# msnanopcb.net
KiCad netlist of a schematic drawn in EAGLE
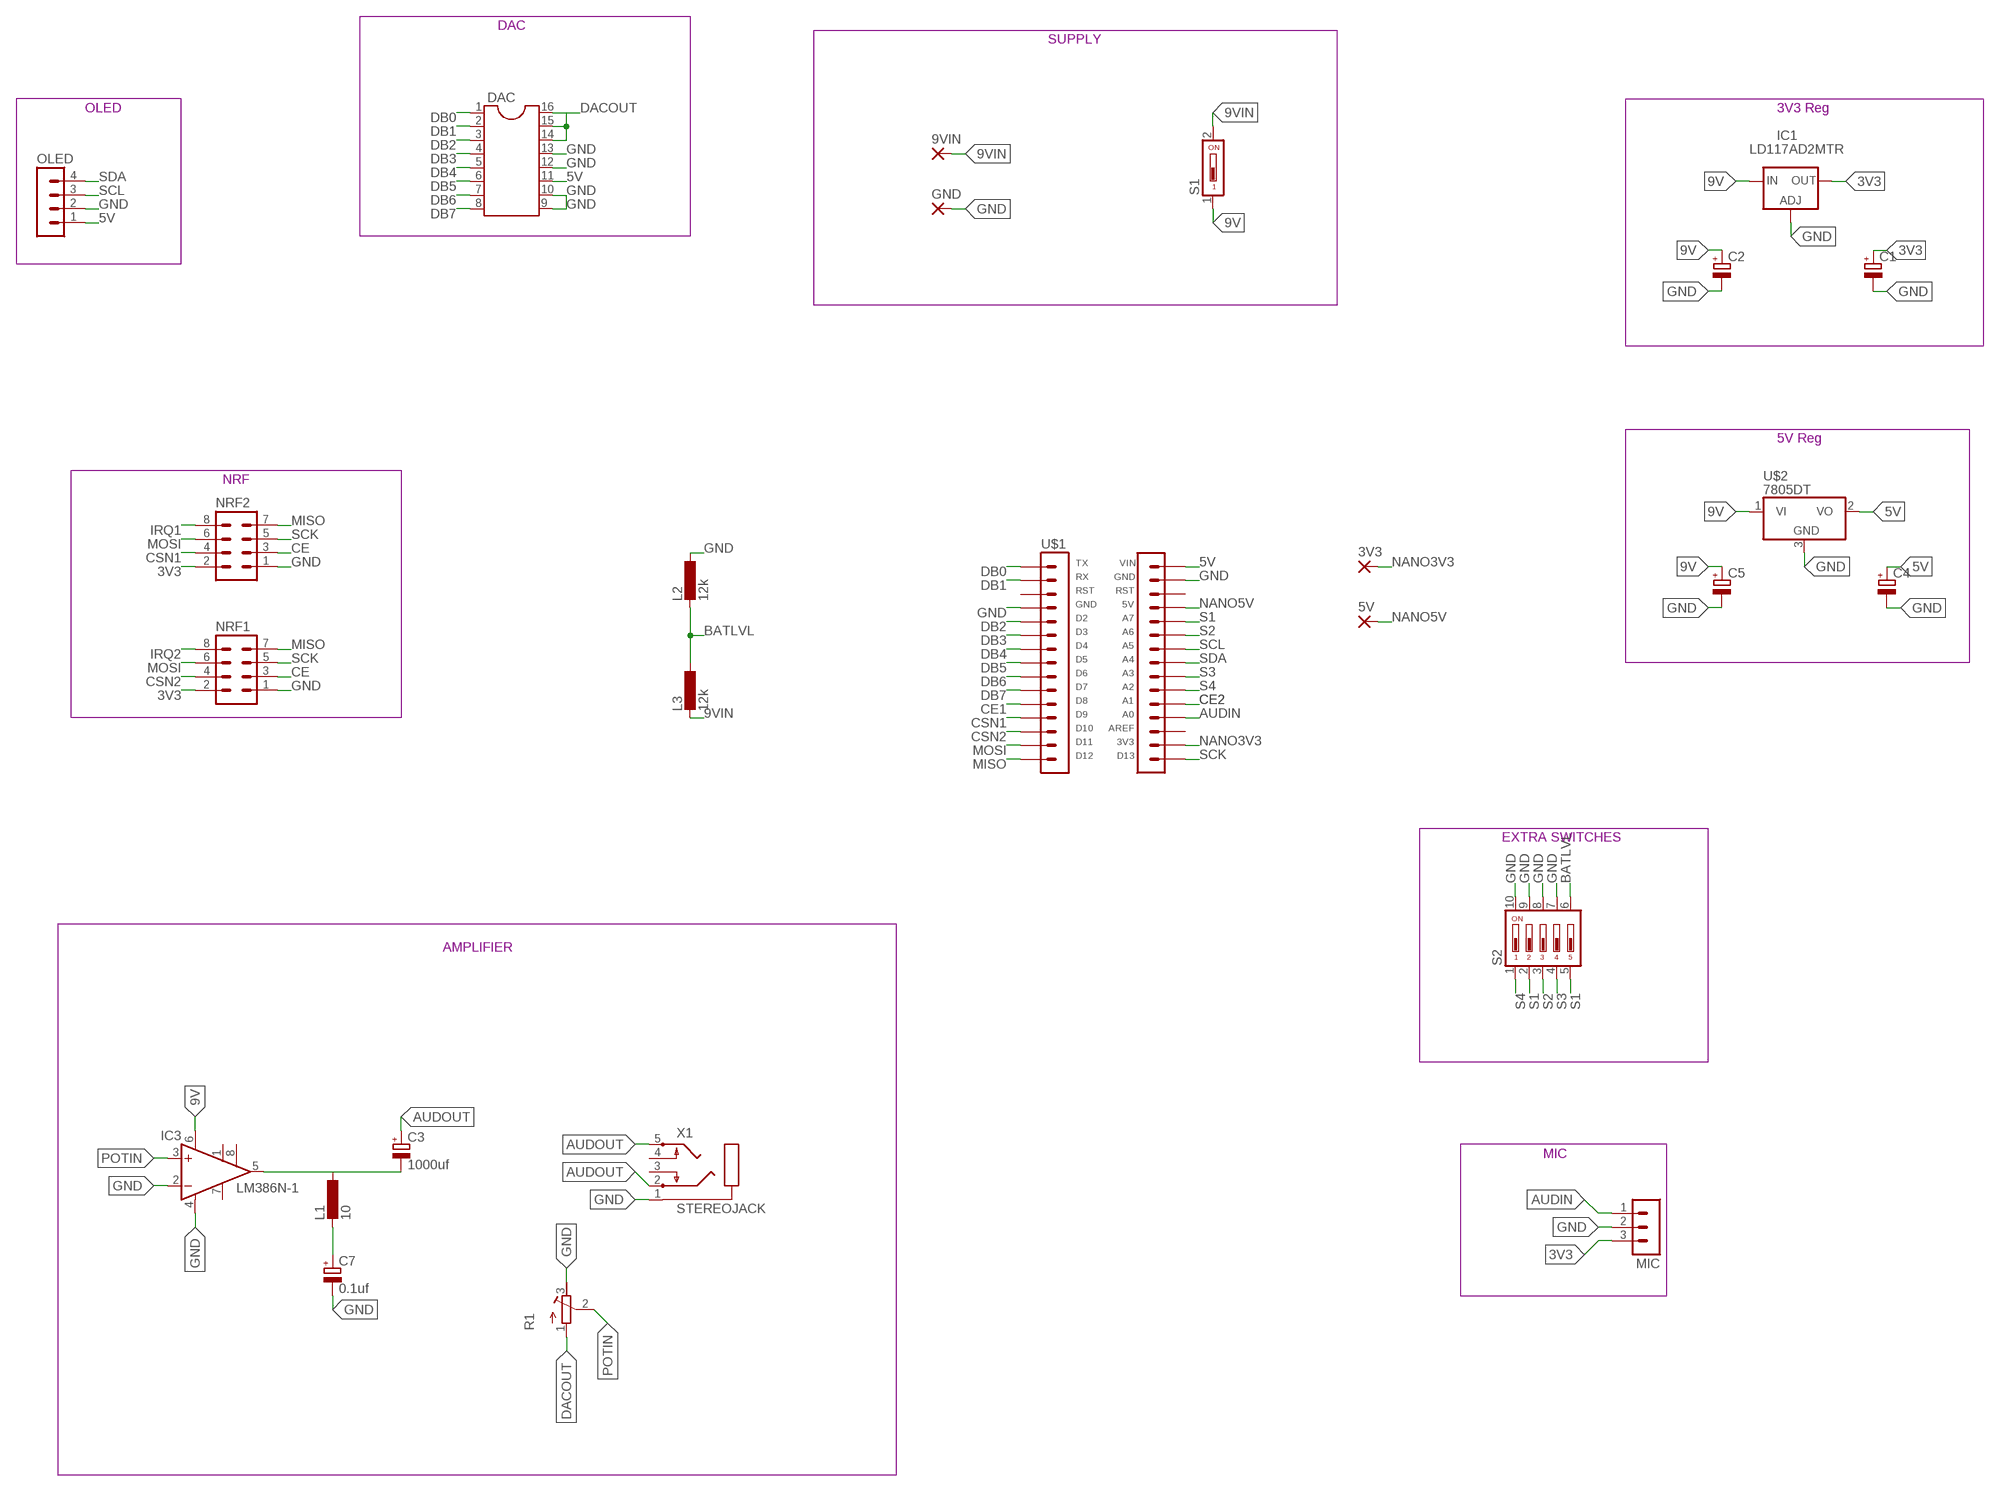
[diagram p0: schematic, sheet 1]

(export (version "E")
  (design (tool "Eeschema 10.0.6"))
  (components
    (comp (ref "3V3")
      (value "WIREPADSMD1,27-254")
      (footprint "eagle-import:SMD1,27-2,54")
      (libsource (lib "eagle-import") (part "WIREPADSMD1,27-254"))
    )
    (comp (ref "5V")
      (value "WIREPADSMD1,27-254")
      (footprint "eagle-import:SMD1,27-2,54")
      (libsource (lib "eagle-import") (part "WIREPADSMD1,27-254"))
    )
    (comp (ref "9VIN")
      (value "WIREPADSMD1,27-254")
      (footprint "eagle-import:SMD1,27-2,54")
      (libsource (lib "eagle-import") (part "WIREPADSMD1,27-254"))
    )
    (comp (ref "C1")
      (value "CPOL-EUE2,5-6E")
      (footprint "eagle-import:E2,5-6E")
      (libsource (lib "eagle-import") (part "CPOL-EUE2,5-6E"))
    )
    (comp (ref "C2")
      (value "CPOL-EUE2,5-6E")
      (footprint "eagle-import:E2,5-6E")
      (libsource (lib "eagle-import") (part "CPOL-EUE2,5-6E"))
    )
    (comp (ref "C3")
      (value "1000uf")
      (footprint "eagle-import:E3,5-8")
      (libsource (lib "eagle-import") (part "CPOL-EUE3.5-8"))
    )
    (comp (ref "C4")
      (value "CPOL-EUE2,5-6E")
      (footprint "eagle-import:E2,5-6E")
      (libsource (lib "eagle-import") (part "CPOL-EUE2,5-6E"))
    )
    (comp (ref "C5")
      (value "CPOL-EUE2,5-6E")
      (footprint "eagle-import:E2,5-6E")
      (libsource (lib "eagle-import") (part "CPOL-EUE2,5-6E"))
    )
    (comp (ref "C7")
      (value "0.1uf")
      (footprint "eagle-import:E2-5")
      (libsource (lib "eagle-import") (part "CPOL-EUE2-5"))
    )
    (comp (ref "DAC")
      (value "DIL16S")
      (footprint "eagle-import:SOCKET-16")
      (libsource (lib "eagle-import") (part "DIL16S"))
    )
    (comp (ref "GND")
      (value "WIREPADSMD1,27-254")
      (footprint "eagle-import:SMD1,27-2,54")
      (libsource (lib "eagle-import") (part "WIREPADSMD1,27-254"))
    )
    (comp (ref "IC1")
      (value "LD117AD2MTR")
      (footprint "eagle-import:D2PACK")
      (libsource (lib "eagle-import") (part "LD117A?D2MTR"))
    )
    (comp (ref "IC3")
      (value "LM386N-1")
      (footprint "eagle-import:DIL08")
      (libsource (lib "eagle-import") (part "LM386?-N1"))
    )
    (comp (ref "L1")
      (value "10")
      (footprint "eagle-import:0204_7")
      (libsource (lib "eagle-import") (part "L-EU0204/7"))
    )
    (comp (ref "L2")
      (value "12k")
      (footprint "eagle-import:0204_7")
      (libsource (lib "eagle-import") (part "L-EU0204/7"))
    )
    (comp (ref "L3")
      (value "12k")
      (footprint "eagle-import:0204_7")
      (libsource (lib "eagle-import") (part "L-EU0204/7"))
    )
    (comp (ref "MIC")
      (value "MA03-1")
      (footprint "eagle-import:MA03-1")
      (libsource (lib "eagle-import") (part "MA03-1"))
    )
    (comp (ref "NRF1")
      (value "MA04-2")
      (footprint "eagle-import:MA04-2")
      (libsource (lib "eagle-import") (part "MA04-2"))
    )
    (comp (ref "NRF2")
      (value "MA04-2")
      (footprint "eagle-import:MA04-2")
      (libsource (lib "eagle-import") (part "MA04-2"))
    )
    (comp (ref "OLED")
      (value "MA04-1")
      (footprint "eagle-import:MA04-1")
      (libsource (lib "eagle-import") (part "MA04-1"))
    )
    (comp (ref "R1")
      (value "R-TRIMM3296P")
      (footprint "eagle-import:RTRIM3296P")
      (libsource (lib "eagle-import") (part "R-TRIMM3296P"))
    )
    (comp (ref "S1")
      (value "DS01")
      (footprint "eagle-import:DS-01")
      (libsource (lib "eagle-import") (part "DS01"))
    )
    (comp (ref "S2")
      (value "DS05")
      (footprint "eagle-import:DS-05")
      (libsource (lib "eagle-import") (part "DS05"))
    )
    (comp (ref "U$1")
      (value "ARD-NANO")
      (footprint "eagle-import:ARD-NANO")
      (libsource (lib "eagle-import") (part "ARD-NANO"))
    )
    (comp (ref "U$2")
      (value "7805DT")
      (footprint "eagle-import:TO252")
      (libsource (lib "eagle-import") (part "78DT05"))
    )
    (comp (ref "X1")
      (value "STEREOJACK")
      (footprint "eagle-import:STX3100")
      (libsource (lib "eagle-import") (part "STEREOJACK"))
    )
  )
  (nets
    (net (code "1") (name "/BATLVL") (class "Default")
      (node (ref "L2") (pin "2") (pinfunction "2_2") (pintype "passive"))
      (node (ref "L3") (pin "1") (pinfunction "1_1") (pintype "passive"))
      (node (ref "S2") (pin "6") (pinfunction "6_6") (pintype "passive"))
    )
    (net (code "2") (name "/CE") (class "Default")
      (node (ref "NRF1") (pin "3") (pinfunction "3_3") (pintype "passive"))
      (node (ref "NRF2") (pin "3") (pinfunction "3_3") (pintype "passive"))
    )
    (net (code "3") (name "/CE1") (class "Default")
      (node (ref "U$1") (pin "D8") (pinfunction "D8_D8") (pintype "passive"))
    )
    (net (code "4") (name "/CE2") (class "Default")
      (node (ref "U$1") (pin "A1") (pinfunction "A1_A1") (pintype "passive"))
    )
    (net (code "5") (name "/CSN1") (class "Default")
      (node (ref "NRF2") (pin "4") (pinfunction "4_4") (pintype "passive"))
      (node (ref "U$1") (pin "D9") (pinfunction "D9_D9") (pintype "passive"))
    )
    (net (code "6") (name "/CSN2") (class "Default")
      (node (ref "NRF1") (pin "4") (pinfunction "4_4") (pintype "passive"))
      (node (ref "U$1") (pin "D10") (pinfunction "D10_D10") (pintype "passive"))
    )
    (net (code "7") (name "/DB0") (class "Default")
      (node (ref "DAC") (pin "1") (pinfunction "1_1") (pintype "passive"))
      (node (ref "U$1") (pin "TX") (pinfunction "TX_TX") (pintype "passive"))
    )
    (net (code "8") (name "/DB1") (class "Default")
      (node (ref "DAC") (pin "2") (pinfunction "2_2") (pintype "passive"))
      (node (ref "U$1") (pin "RX") (pinfunction "RX_RX") (pintype "passive"))
    )
    (net (code "9") (name "/DB2") (class "Default")
      (node (ref "DAC") (pin "3") (pinfunction "3_3") (pintype "passive"))
      (node (ref "U$1") (pin "D2") (pinfunction "D2_D2") (pintype "passive"))
    )
    (net (code "10") (name "/DB3") (class "Default")
      (node (ref "DAC") (pin "4") (pinfunction "4_4") (pintype "passive"))
      (node (ref "U$1") (pin "D3") (pinfunction "D3_D3") (pintype "passive"))
    )
    (net (code "11") (name "/DB4") (class "Default")
      (node (ref "DAC") (pin "5") (pinfunction "5_5") (pintype "passive"))
      (node (ref "U$1") (pin "D4") (pinfunction "D4_D4") (pintype "passive"))
    )
    (net (code "12") (name "/DB5") (class "Default")
      (node (ref "DAC") (pin "6") (pinfunction "6_6") (pintype "passive"))
      (node (ref "U$1") (pin "D5") (pinfunction "D5_D5") (pintype "passive"))
    )
    (net (code "13") (name "/DB6") (class "Default")
      (node (ref "DAC") (pin "7") (pinfunction "7_7") (pintype "passive"))
      (node (ref "U$1") (pin "D6") (pinfunction "D6_D6") (pintype "passive"))
    )
    (net (code "14") (name "/DB7") (class "Default")
      (node (ref "DAC") (pin "8") (pinfunction "8_8") (pintype "passive"))
      (node (ref "U$1") (pin "D7") (pinfunction "D7_D7") (pintype "passive"))
    )
    (net (code "15") (name "/IRQ1") (class "Default")
      (node (ref "NRF2") (pin "8") (pinfunction "8_8") (pintype "passive"))
    )
    (net (code "16") (name "/IRQ2") (class "Default")
      (node (ref "NRF1") (pin "8") (pinfunction "8_8") (pintype "passive"))
    )
    (net (code "17") (name "/MISO") (class "Default")
      (node (ref "NRF1") (pin "7") (pinfunction "7_7") (pintype "passive"))
      (node (ref "NRF2") (pin "7") (pinfunction "7_7") (pintype "passive"))
      (node (ref "U$1") (pin "D12") (pinfunction "D12_D12") (pintype "passive"))
    )
    (net (code "18") (name "/MOSI") (class "Default")
      (node (ref "NRF1") (pin "6") (pinfunction "6_6") (pintype "passive"))
      (node (ref "NRF2") (pin "6") (pinfunction "6_6") (pintype "passive"))
      (node (ref "U$1") (pin "D11") (pinfunction "D11_D11") (pintype "passive"))
    )
    (net (code "19") (name "/NANO3V3") (class "Default")
      (node (ref "3V3") (pin "1") (pinfunction "P_1") (pintype "passive"))
      (node (ref "U$1") (pin "3V3") (pinfunction "3V3_3V3") (pintype "passive"))
    )
    (net (code "20") (name "/NANO5V") (class "Default")
      (node (ref "5V") (pin "1") (pinfunction "P_1") (pintype "passive"))
      (node (ref "U$1") (pin "5V") (pinfunction "5V_5V") (pintype "passive"))
    )
    (net (code "21") (name "/S1") (class "Default")
      (node (ref "S2") (pin "2") (pinfunction "2_2") (pintype "passive"))
      (node (ref "S2") (pin "5") (pinfunction "5_5") (pintype "passive"))
      (node (ref "U$1") (pin "A7") (pinfunction "A7_A7") (pintype "passive"))
    )
    (net (code "22") (name "/S2") (class "Default")
      (node (ref "S2") (pin "3") (pinfunction "3_3") (pintype "passive"))
      (node (ref "U$1") (pin "A6") (pinfunction "A6_A6") (pintype "passive"))
    )
    (net (code "23") (name "/S3") (class "Default")
      (node (ref "S2") (pin "4") (pinfunction "4_4") (pintype "passive"))
      (node (ref "U$1") (pin "A3") (pinfunction "A3_A3") (pintype "passive"))
    )
    (net (code "24") (name "/S4") (class "Default")
      (node (ref "S2") (pin "1") (pinfunction "1_1") (pintype "passive"))
      (node (ref "U$1") (pin "A2") (pinfunction "A2_A2") (pintype "passive"))
    )
    (net (code "25") (name "/SCK") (class "Default")
      (node (ref "NRF1") (pin "5") (pinfunction "5_5") (pintype "passive"))
      (node (ref "NRF2") (pin "5") (pinfunction "5_5") (pintype "passive"))
      (node (ref "U$1") (pin "D13") (pinfunction "D13_D13") (pintype "passive"))
    )
    (net (code "26") (name "/SCL") (class "Default")
      (node (ref "OLED") (pin "3") (pinfunction "3_3") (pintype "passive"))
      (node (ref "U$1") (pin "A5") (pinfunction "A5_A5") (pintype "passive"))
    )
    (net (code "27") (name "/SDA") (class "Default")
      (node (ref "OLED") (pin "4") (pinfunction "4_4") (pintype "passive"))
      (node (ref "U$1") (pin "A4") (pinfunction "A4_A4") (pintype "passive"))
    )
    (net (code "28") (name "3V3") (class "Default")
      (node (ref "C1") (pin "+") (pinfunction "+_+") (pintype "passive"))
      (node (ref "IC1") (pin "2") (pinfunction "OUT_2") (pintype "passive"))
      (node (ref "MIC") (pin "3") (pinfunction "3_3") (pintype "passive"))
      (node (ref "NRF1") (pin "2") (pinfunction "2_2") (pintype "passive"))
      (node (ref "NRF2") (pin "2") (pinfunction "2_2") (pintype "passive"))
    )
    (net (code "29") (name "5V") (class "Default")
      (node (ref "C4") (pin "+") (pinfunction "+_+") (pintype "passive"))
      (node (ref "DAC") (pin "11") (pinfunction "11_11") (pintype "passive"))
      (node (ref "OLED") (pin "1") (pinfunction "1_1") (pintype "passive"))
      (node (ref "U$1") (pin "VIN") (pinfunction "VIN_VIN") (pintype "passive"))
      (node (ref "U$2") (pin "2") (pinfunction "VO_2") (pintype "passive"))
    )
    (net (code "30") (name "9V") (class "Default")
      (node (ref "C2") (pin "+") (pinfunction "+_+") (pintype "passive"))
      (node (ref "C5") (pin "+") (pinfunction "+_+") (pintype "passive"))
      (node (ref "IC1") (pin "3") (pinfunction "IN_3") (pintype "input"))
      (node (ref "IC3") (pin "6") (pinfunction "VS_6") (pintype "power_in"))
      (node (ref "S1") (pin "1") (pinfunction "1_1") (pintype "passive"))
      (node (ref "U$2") (pin "1") (pinfunction "VI_1") (pintype "input"))
    )
    (net (code "31") (name "9VIN") (class "Default")
      (node (ref "9VIN") (pin "1") (pinfunction "P_1") (pintype "passive"))
      (node (ref "L3") (pin "2") (pinfunction "2_2") (pintype "passive"))
      (node (ref "S1") (pin "2") (pinfunction "2_2") (pintype "passive"))
    )
    (net (code "32") (name "AUDIN") (class "Default")
      (node (ref "MIC") (pin "1") (pinfunction "1_1") (pintype "passive"))
      (node (ref "U$1") (pin "A0") (pinfunction "A0_A0") (pintype "passive"))
    )
    (net (code "33") (name "AUDOUT") (class "Default")
      (node (ref "C3") (pin "+") (pinfunction "+_+") (pintype "passive"))
      (node (ref "X1") (pin "2") (pinfunction "2_2") (pintype "passive"))
      (node (ref "X1") (pin "5") (pinfunction "5_5") (pintype "passive"))
    )
    (net (code "34") (name "DACOUT") (class "Default")
      (node (ref "DAC") (pin "14") (pinfunction "14_14") (pintype "passive"))
      (node (ref "DAC") (pin "15") (pinfunction "15_15") (pintype "passive"))
      (node (ref "DAC") (pin "16") (pinfunction "16_16") (pintype "passive"))
      (node (ref "R1") (pin "1") (pinfunction "A_1") (pintype "passive"))
    )
    (net (code "35") (name "GND") (class "Default")
      (node (ref "C1") (pin "-") (pinfunction "-_-") (pintype "passive"))
      (node (ref "C2") (pin "-") (pinfunction "-_-") (pintype "passive"))
      (node (ref "C4") (pin "-") (pinfunction "-_-") (pintype "passive"))
      (node (ref "C5") (pin "-") (pinfunction "-_-") (pintype "passive"))
      (node (ref "C7") (pin "-") (pinfunction "-_-") (pintype "passive"))
      (node (ref "DAC") (pin "10") (pinfunction "10_10") (pintype "passive"))
      (node (ref "DAC") (pin "12") (pinfunction "12_12") (pintype "passive"))
      (node (ref "DAC") (pin "13") (pinfunction "13_13") (pintype "passive"))
      (node (ref "DAC") (pin "9") (pinfunction "9_9") (pintype "passive"))
      (node (ref "GND") (pin "1") (pinfunction "P_1") (pintype "passive"))
      (node (ref "IC1") (pin "1") (pinfunction "ADJ_1") (pintype "input"))
      (node (ref "IC3") (pin "2") (pinfunction "-IN_2") (pintype "input"))
      (node (ref "IC3") (pin "4") (pinfunction "GND_4") (pintype "power_in"))
      (node (ref "L2") (pin "1") (pinfunction "1_1") (pintype "passive"))
      (node (ref "MIC") (pin "2") (pinfunction "2_2") (pintype "passive"))
      (node (ref "NRF1") (pin "1") (pinfunction "1_1") (pintype "passive"))
      (node (ref "NRF2") (pin "1") (pinfunction "1_1") (pintype "passive"))
      (node (ref "OLED") (pin "2") (pinfunction "2_2") (pintype "passive"))
      (node (ref "R1") (pin "3") (pinfunction "E_3") (pintype "passive"))
      (node (ref "S2") (pin "10") (pinfunction "10_10") (pintype "passive"))
      (node (ref "S2") (pin "7") (pinfunction "7_7") (pintype "passive"))
      (node (ref "S2") (pin "8") (pinfunction "8_8") (pintype "passive"))
      (node (ref "S2") (pin "9") (pinfunction "9_9") (pintype "passive"))
      (node (ref "U$1") (pin "GND1") (pinfunction "GND1_GND1") (pintype "passive"))
      (node (ref "U$1") (pin "GND2") (pinfunction "GND2_GND2") (pintype "passive"))
      (node (ref "U$2") (pin "3") (pinfunction "GND_3") (pintype "passive"))
      (node (ref "X1") (pin "1") (pinfunction "1_1") (pintype "passive"))
    )
    (net (code "36") (name "Net-(C7-Pad+)") (class "Default")
      (node (ref "C7") (pin "+") (pinfunction "+_+") (pintype "passive"))
      (node (ref "L1") (pin "2") (pinfunction "2_2") (pintype "passive"))
    )
    (net (code "37") (name "Net-(IC3-OUT)") (class "Default")
      (node (ref "C3") (pin "-") (pinfunction "-_-") (pintype "passive"))
      (node (ref "IC3") (pin "5") (pinfunction "OUT_5") (pintype "output"))
      (node (ref "L1") (pin "1") (pinfunction "1_1") (pintype "passive"))
    )
    (net (code "38") (name "POTIN") (class "Default")
      (node (ref "IC3") (pin "3") (pinfunction "+IN_3") (pintype "input"))
      (node (ref "R1") (pin "2") (pinfunction "S_2") (pintype "passive"))
    )
    (net (code "39") (name "unconnected-(IC3-BYPASS-Pad7)") (class "Default")
      (node (ref "IC3") (pin "7") (pinfunction "BYPASS_7") (pintype "passive"))
    )
    (net (code "40") (name "unconnected-(IC3-GAIN-Pad1)") (class "Default")
      (node (ref "IC3") (pin "1") (pinfunction "GAIN_1") (pintype "passive"))
    )
    (net (code "41") (name "unconnected-(IC3-GAIN-Pad8)") (class "Default")
      (node (ref "IC3") (pin "8") (pinfunction "GAIN_8") (pintype "passive"))
    )
    (net (code "42") (name "unconnected-(U$1-PadAREF)") (class "Default")
      (node (ref "U$1") (pin "AREF") (pinfunction "AREF_AREF") (pintype "passive"))
    )
    (net (code "43") (name "unconnected-(U$1-PadRST1)") (class "Default")
      (node (ref "U$1") (pin "RST1") (pinfunction "RST1_RST1") (pintype "passive"))
    )
    (net (code "44") (name "unconnected-(U$1-PadRST2)") (class "Default")
      (node (ref "U$1") (pin "RST2") (pinfunction "RST2_RST2") (pintype "passive"))
    )
    (net (code "45") (name "unconnected-(X1-Pad3)") (class "Default")
      (node (ref "X1") (pin "3") (pinfunction "3_3") (pintype "passive"))
    )
    (net (code "46") (name "unconnected-(X1-Pad4)") (class "Default")
      (node (ref "X1") (pin "4") (pinfunction "4_4") (pintype "passive"))
    )
  )
)
